# cw312_sam4s.net
KiCad netlist of a schematic drawn in Altium Designer
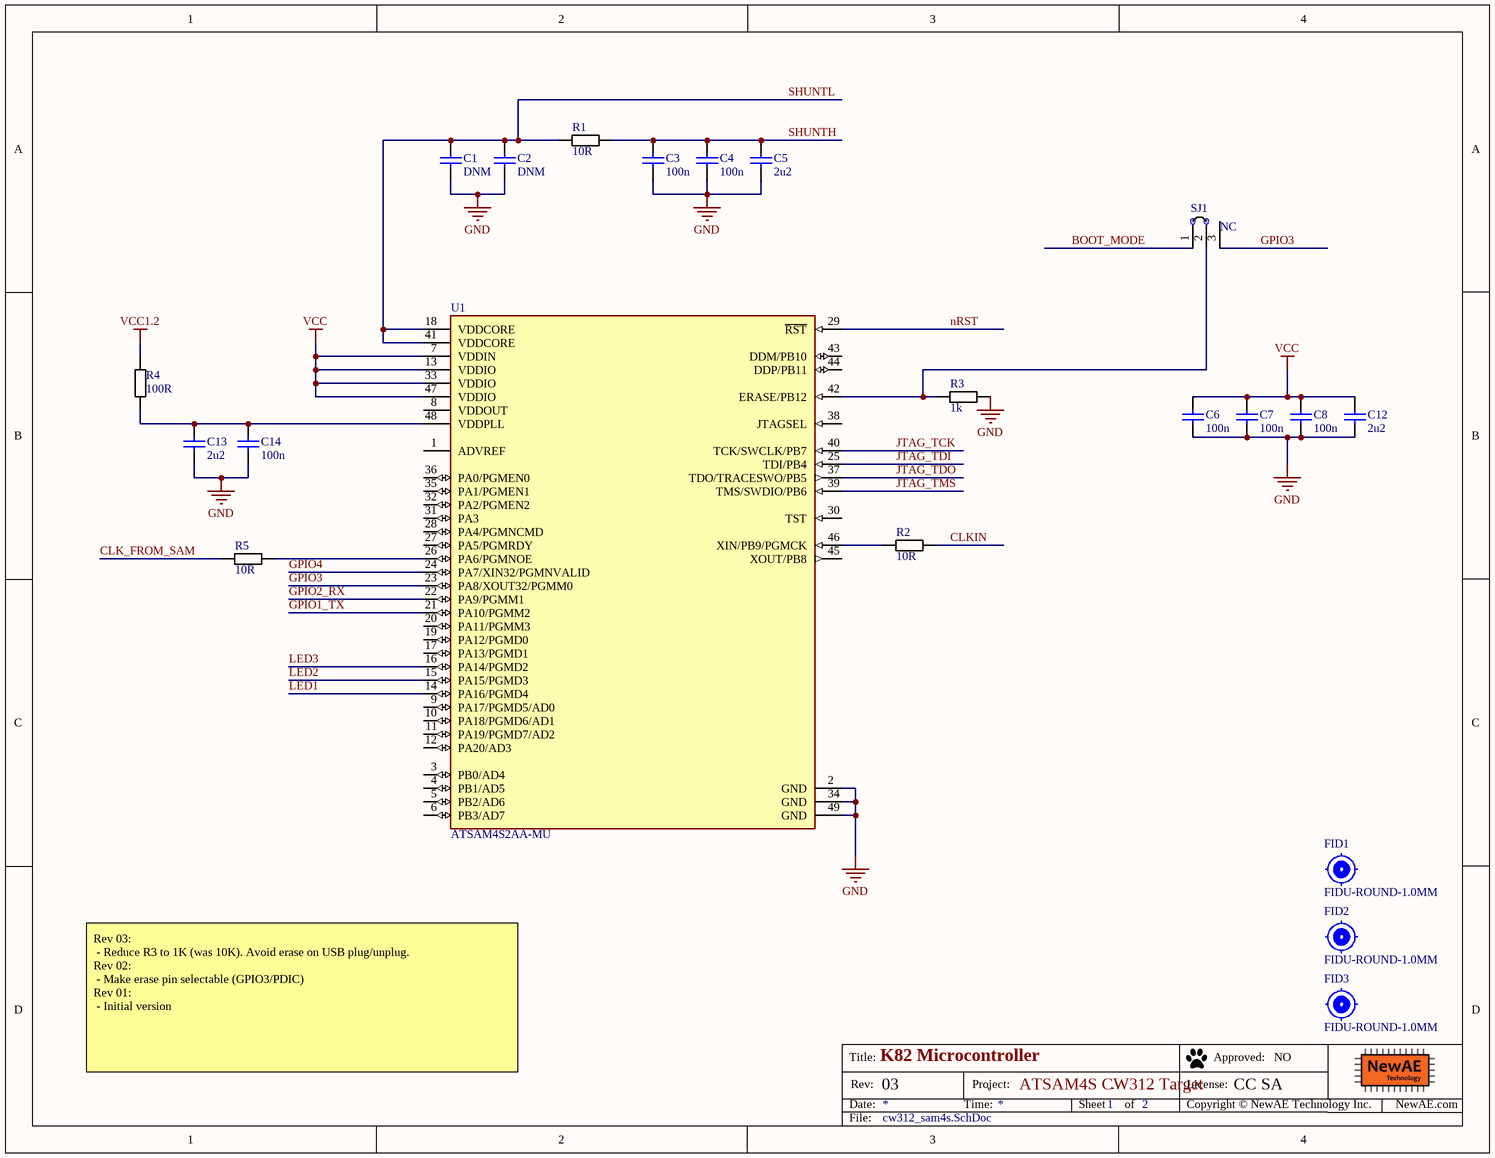
[diagram p0: cw312_sam4s.SchDoc]

(export (version "E")
  (design (tool "Eeschema 10.0.6"))
  (components
    (comp (ref "C1")
      (value "DNM")
      (footprint "CAPC0603_M")
      (fields (field (name "PART NUMBER") "CCHIP-100n-0603"))
      (libsource (lib "NewAE_AltiumLib") (part "CAP"))
    )
    (comp (ref "C2")
      (value "DNM")
      (footprint "CAPC0603_M")
      (fields (field (name "PART NUMBER") "CCHIP-100n-0603"))
      (libsource (lib "NewAE_AltiumLib") (part "CAP"))
    )
    (comp (ref "C3")
      (value "100n")
      (footprint "CAPC0603_M")
      (description "100n, 0603")
      (fields (field (name "PART NUMBER") "CCHIP-100n-0603"))
      (libsource (lib "NewAE_AltiumLib") (part "CAP"))
    )
    (comp (ref "C4")
      (value "100n")
      (footprint "CAPC0603_M")
      (description "100n, 0603")
      (fields (field (name "PART NUMBER") "CCHIP-100n-0603"))
      (libsource (lib "NewAE_AltiumLib") (part "CAP"))
    )
    (comp (ref "C5")
      (value "2u2")
      (footprint "CAPC0603_M")
      (description "2u2, 0603")
      (fields (field (name "PART NUMBER") "CCHIP-2u2-0603"))
      (libsource (lib "NewAE_AltiumLib") (part "CAP"))
    )
    (comp (ref "C6")
      (value "100n")
      (footprint "CAPC0603_M")
      (description "100n, 0603")
      (fields (field (name "PART NUMBER") "CCHIP-100n-0603"))
      (libsource (lib "NewAE_AltiumLib") (part "CAP"))
    )
    (comp (ref "C7")
      (value "100n")
      (footprint "CAPC0603_M")
      (description "100n, 0603")
      (fields (field (name "PART NUMBER") "CCHIP-100n-0603"))
      (libsource (lib "NewAE_AltiumLib") (part "CAP"))
    )
    (comp (ref "C8")
      (value "100n")
      (footprint "CAPC0603_M")
      (description "100n, 0603")
      (fields (field (name "PART NUMBER") "CCHIP-100n-0603"))
      (libsource (lib "NewAE_AltiumLib") (part "CAP"))
    )
    (comp (ref "C12")
      (value "2u2")
      (footprint "CAPC0603_M")
      (description "2u2, 0603")
      (fields (field (name "PART NUMBER") "CCHIP-2u2-0603"))
      (libsource (lib "NewAE_AltiumLib") (part "CAP"))
    )
    (comp (ref "C13")
      (value "2u2")
      (footprint "CAPC0603_M")
      (description "2u2, 0603")
      (fields (field (name "PART NUMBER") "CCHIP-2u2-0603"))
      (libsource (lib "NewAE_AltiumLib") (part "CAP"))
    )
    (comp (ref "C14")
      (value "100n")
      (footprint "CAPC0603_M")
      (description "100n, 0603")
      (fields (field (name "PART NUMBER") "CCHIP-100n-0603"))
      (libsource (lib "NewAE_AltiumLib") (part "CAP"))
    )
    (comp (ref "FID1")
      (value "FIDU-ROUND-1.0MM")
      (footprint "FIDU-ROUND-1.0mm")
      (description "ROUND FIDUCIAL")
      (libsource (lib "NewAE_AltiumLib") (part "FIDU-ROUND-1.0MM"))
    )
    (comp (ref "FID2")
      (value "FIDU-ROUND-1.0MM")
      (footprint "FIDU-ROUND-1.0mm")
      (description "ROUND FIDUCIAL")
      (libsource (lib "NewAE_AltiumLib") (part "FIDU-ROUND-1.0MM"))
    )
    (comp (ref "FID3")
      (value "FIDU-ROUND-1.0MM")
      (footprint "FIDU-ROUND-1.0mm")
      (description "ROUND FIDUCIAL")
      (libsource (lib "NewAE_AltiumLib") (part "FIDU-ROUND-1.0MM"))
    )
    (comp (ref "R1")
      (value "10R")
      (footprint "RESC1608X55N")
      (description "10R res, 0603, 1%, 1/10W")
      (fields (field (name "PART NUMBER") "RCHIP-10R-0603") (field (name "TOLERANCE") "1%"))
      (libsource (lib "") (part "RES-EU_1"))
    )
    (comp (ref "R2")
      (value "10R")
      (footprint "RESC1608X55N")
      (description "10R res, 0603, 1%, 1/10W")
      (fields (field (name "PART NUMBER") "RCHIP-10R-0603") (field (name "TOLERANCE") "1%"))
      (libsource (lib "NewAE_AltiumLib") (part "RES-EU"))
    )
    (comp (ref "R3")
      (value "1k")
      (footprint "RESC1608X55N")
      (description "1k res, 0603, 1%, 1/10W")
      (fields (field (name "PART NUMBER") "RCHIP-1K-0603") (field (name "TOLERANCE") "1%"))
      (libsource (lib "") (part "RES-EU_1"))
    )
    (comp (ref "R4")
      (value "100R")
      (footprint "RESC1608X55N")
      (description "100R res, 0603, 1%, 1/10W")
      (fields (field (name "PART NUMBER") "RCHIP-100R-0603") (field (name "TOLERANCE") "1%"))
      (libsource (lib "") (part "RES-EU_2"))
    )
    (comp (ref "R5")
      (value "10R")
      (footprint "RESC1608X55N")
      (description "10R res, 0603, 1%, 1/10W")
      (fields (field (name "PART NUMBER") "RCHIP-10R-0603") (field (name "TOLERANCE") "1%"))
      (libsource (lib "NewAE_AltiumLib") (part "RES-EU"))
    )
    (comp (ref "SJ1")
      (value "NC")
      (footprint "SJ_3S_NC12")
      (description "Solder Jumper, NC")
      (fields (field (name "PART NUMBER") "SJ_3S_12JMP"))
      (libsource (lib "NewAE_AltiumLib") (part "SJ_3S_12JMP"))
    )
    (comp (ref "U1")
      (value "ATSAM4S2AA-MU")
      (footprint "QFN50P700X700X100_HS-49M")
      (description "ATSAM4S, 128KB FLASH, 48QFN")
      (libsource (lib "NewAE_AltiumLib") (part "ATSAM4S2AA"))
    )
  )
  (nets
    (net (code "1") (name "/BOOT_MODE") (class "Default")
      (node (ref "SJ1") (pin "1") (pinfunction "1_1") (pintype "passive"))
    )
    (net (code "2") (name "/CLKIN") (class "Default")
      (node (ref "R2") (pin "1") (pinfunction "1_1") (pintype "passive"))
    )
    (net (code "3") (name "/CLK_FROM_SAM") (class "Default")
      (node (ref "R5") (pin "2") (pinfunction "2_2") (pintype "passive"))
    )
    (net (code "4") (name "/GPIO1_TX") (class "Default")
      (node (ref "U1") (pin "21") (pinfunction "PA10/PGMM2_21") (pintype "bidirectional"))
    )
    (net (code "5") (name "/GPIO2_RX") (class "Default")
      (node (ref "U1") (pin "22") (pinfunction "PA9/PGMM1_22") (pintype "bidirectional"))
    )
    (net (code "6") (name "/GPIO3") (class "Default")
      (node (ref "SJ1") (pin "3") (pinfunction "3_3") (pintype "passive"))
      (node (ref "U1") (pin "23") (pinfunction "PA8/XOUT32/PGMM0_23") (pintype "bidirectional"))
    )
    (net (code "7") (name "/GPIO4") (class "Default")
      (node (ref "U1") (pin "24") (pinfunction "PA7/XIN32/PGMNVALID_24") (pintype "bidirectional"))
    )
    (net (code "8") (name "/JTAG_TCK") (class "Default")
      (node (ref "U1") (pin "40") (pinfunction "TCK/SWCLK/PB7_40") (pintype "input"))
    )
    (net (code "9") (name "/JTAG_TDI") (class "Default")
      (node (ref "U1") (pin "25") (pinfunction "TDI/PB4_25") (pintype "input"))
    )
    (net (code "10") (name "/JTAG_TDO") (class "Default")
      (node (ref "U1") (pin "37") (pinfunction "TDO/TRACESWO/PB5_37") (pintype "output"))
    )
    (net (code "11") (name "/JTAG_TMS") (class "Default")
      (node (ref "U1") (pin "39") (pinfunction "TMS/SWDIO/PB6_39") (pintype "input"))
    )
    (net (code "12") (name "/LED1") (class "Default")
      (node (ref "U1") (pin "14") (pinfunction "PA16/PGMD4_14") (pintype "bidirectional"))
    )
    (net (code "13") (name "/LED2") (class "Default")
      (node (ref "U1") (pin "15") (pinfunction "PA15/PGMD3_15") (pintype "bidirectional"))
    )
    (net (code "14") (name "/LED3") (class "Default")
      (node (ref "U1") (pin "16") (pinfunction "PA14/PGMD2_16") (pintype "bidirectional"))
    )
    (net (code "15") (name "/SHUNTH") (class "Default")
      (node (ref "C3") (pin "1") (pinfunction "1_1") (pintype "passive"))
      (node (ref "C4") (pin "1") (pinfunction "1_1") (pintype "passive"))
      (node (ref "C5") (pin "1") (pinfunction "1_1") (pintype "passive"))
      (node (ref "R1") (pin "2") (pinfunction "2_2") (pintype "passive"))
    )
    (net (code "16") (name "/SHUNTL") (class "Default")
      (node (ref "C1") (pin "1") (pinfunction "1_1") (pintype "passive"))
      (node (ref "C2") (pin "1") (pinfunction "1_1") (pintype "passive"))
      (node (ref "R1") (pin "1") (pinfunction "1_1") (pintype "passive"))
      (node (ref "U1") (pin "18") (pinfunction "VDDCORE_18") (pintype "power_in"))
      (node (ref "U1") (pin "41") (pinfunction "VDDCORE_41") (pintype "power_in"))
    )
    (net (code "17") (name "/nRST") (class "Default")
      (node (ref "U1") (pin "29") (pinfunction "~{RST}_29") (pintype "input"))
    )
    (net (code "18") (name "GND") (class "Default")
      (node (ref "C1") (pin "2") (pinfunction "2_2") (pintype "passive"))
      (node (ref "C12") (pin "2") (pinfunction "2_2") (pintype "passive"))
      (node (ref "C13") (pin "2") (pinfunction "2_2") (pintype "passive"))
      (node (ref "C14") (pin "2") (pinfunction "2_2") (pintype "passive"))
      (node (ref "C2") (pin "2") (pinfunction "2_2") (pintype "passive"))
      (node (ref "C3") (pin "2") (pinfunction "2_2") (pintype "passive"))
      (node (ref "C4") (pin "2") (pinfunction "2_2") (pintype "passive"))
      (node (ref "C5") (pin "2") (pinfunction "2_2") (pintype "passive"))
      (node (ref "C6") (pin "2") (pinfunction "2_2") (pintype "passive"))
      (node (ref "C7") (pin "2") (pinfunction "2_2") (pintype "passive"))
      (node (ref "C8") (pin "2") (pinfunction "2_2") (pintype "passive"))
      (node (ref "R3") (pin "2") (pinfunction "2_2") (pintype "passive"))
      (node (ref "U1") (pin "2") (pinfunction "GND_2") (pintype "power_in"))
      (node (ref "U1") (pin "34") (pinfunction "GND_34") (pintype "power_in"))
      (node (ref "U1") (pin "49") (pinfunction "GND_49") (pintype "power_in"))
    )
    (net (code "19") (name "Net-(U1-ERASE{slash}PB12)") (class "Default")
      (node (ref "R3") (pin "1") (pinfunction "1_1") (pintype "passive"))
      (node (ref "SJ1") (pin "2") (pinfunction "2_2") (pintype "passive"))
      (node (ref "U1") (pin "42") (pinfunction "ERASE/PB12_42") (pintype "input"))
    )
    (net (code "20") (name "Net-(U1-PA6{slash}PGMNOE)") (class "Default")
      (node (ref "R5") (pin "1") (pinfunction "1_1") (pintype "passive"))
      (node (ref "U1") (pin "26") (pinfunction "PA6/PGMNOE_26") (pintype "bidirectional"))
    )
    (net (code "21") (name "Net-(U1-VDDPLL)") (class "Default")
      (node (ref "C13") (pin "1") (pinfunction "1_1") (pintype "passive"))
      (node (ref "C14") (pin "1") (pinfunction "1_1") (pintype "passive"))
      (node (ref "R4") (pin "2") (pinfunction "2_2") (pintype "passive"))
      (node (ref "U1") (pin "48") (pinfunction "VDDPLL_48") (pintype "power_in"))
    )
    (net (code "22") (name "Net-(U1-XIN{slash}PB9{slash}PGMCK)") (class "Default")
      (node (ref "R2") (pin "2") (pinfunction "2_2") (pintype "passive"))
      (node (ref "U1") (pin "46") (pinfunction "XIN/PB9/PGMCK_46") (pintype "input"))
    )
    (net (code "23") (name "VCC") (class "Default")
      (node (ref "C12") (pin "1") (pinfunction "1_1") (pintype "passive"))
      (node (ref "C6") (pin "1") (pinfunction "1_1") (pintype "passive"))
      (node (ref "C7") (pin "1") (pinfunction "1_1") (pintype "passive"))
      (node (ref "C8") (pin "1") (pinfunction "1_1") (pintype "passive"))
      (node (ref "U1") (pin "13") (pinfunction "VDDIO_13") (pintype "power_in"))
      (node (ref "U1") (pin "33") (pinfunction "VDDIO_33") (pintype "power_in"))
      (node (ref "U1") (pin "47") (pinfunction "VDDIO_47") (pintype "power_in"))
      (node (ref "U1") (pin "7") (pinfunction "VDDIN_7") (pintype "power_in"))
    )
    (net (code "24") (name "VCC1.2") (class "Default")
      (node (ref "R4") (pin "1") (pinfunction "1_1") (pintype "passive"))
    )
    (net (code "25") (name "unconnected-(U1-ADVREF-Pad1)") (class "Default")
      (node (ref "U1") (pin "1") (pinfunction "ADVREF_1") (pintype "power_in"))
    )
    (net (code "26") (name "unconnected-(U1-DDM{slash}PB10-Pad43)") (class "Default")
      (node (ref "U1") (pin "43") (pinfunction "DDM/PB10_43") (pintype "bidirectional"))
    )
    (net (code "27") (name "unconnected-(U1-DDP{slash}PB11-Pad44)") (class "Default")
      (node (ref "U1") (pin "44") (pinfunction "DDP/PB11_44") (pintype "bidirectional"))
    )
    (net (code "28") (name "unconnected-(U1-JTAGSEL-Pad38)") (class "Default")
      (node (ref "U1") (pin "38") (pinfunction "JTAGSEL_38") (pintype "input"))
    )
    (net (code "29") (name "unconnected-(U1-PA0{slash}PGMEN0-Pad36)") (class "Default")
      (node (ref "U1") (pin "36") (pinfunction "PA0/PGMEN0_36") (pintype "bidirectional"))
    )
    (net (code "30") (name "unconnected-(U1-PA1{slash}PGMEN1-Pad35)") (class "Default")
      (node (ref "U1") (pin "35") (pinfunction "PA1/PGMEN1_35") (pintype "bidirectional"))
    )
    (net (code "31") (name "unconnected-(U1-PA2{slash}PGMEN2-Pad32)") (class "Default")
      (node (ref "U1") (pin "32") (pinfunction "PA2/PGMEN2_32") (pintype "bidirectional"))
    )
    (net (code "32") (name "unconnected-(U1-PA3-Pad31)") (class "Default")
      (node (ref "U1") (pin "31") (pinfunction "PA3_31") (pintype "bidirectional"))
    )
    (net (code "33") (name "unconnected-(U1-PA4{slash}PGMNCMD-Pad28)") (class "Default")
      (node (ref "U1") (pin "28") (pinfunction "PA4/PGMNCMD_28") (pintype "bidirectional"))
    )
    (net (code "34") (name "unconnected-(U1-PA5{slash}PGMRDY-Pad27)") (class "Default")
      (node (ref "U1") (pin "27") (pinfunction "PA5/PGMRDY_27") (pintype "bidirectional"))
    )
    (net (code "35") (name "unconnected-(U1-PA11{slash}PGMM3-Pad20)") (class "Default")
      (node (ref "U1") (pin "20") (pinfunction "PA11/PGMM3_20") (pintype "bidirectional"))
    )
    (net (code "36") (name "unconnected-(U1-PA12{slash}PGMD0-Pad19)") (class "Default")
      (node (ref "U1") (pin "19") (pinfunction "PA12/PGMD0_19") (pintype "bidirectional"))
    )
    (net (code "37") (name "unconnected-(U1-PA13{slash}PGMD1-Pad17)") (class "Default")
      (node (ref "U1") (pin "17") (pinfunction "PA13/PGMD1_17") (pintype "bidirectional"))
    )
    (net (code "38") (name "unconnected-(U1-PA17{slash}PGMD5{slash}AD0-Pad9)") (class "Default")
      (node (ref "U1") (pin "9") (pinfunction "PA17/PGMD5/AD0_9") (pintype "bidirectional"))
    )
    (net (code "39") (name "unconnected-(U1-PA18{slash}PGMD6{slash}AD1-Pad10)") (class "Default")
      (node (ref "U1") (pin "10") (pinfunction "PA18/PGMD6/AD1_10") (pintype "bidirectional"))
    )
    (net (code "40") (name "unconnected-(U1-PA19{slash}PGMD7{slash}AD2-Pad11)") (class "Default")
      (node (ref "U1") (pin "11") (pinfunction "PA19/PGMD7/AD2_11") (pintype "bidirectional"))
    )
    (net (code "41") (name "unconnected-(U1-PA20{slash}AD3-Pad12)") (class "Default")
      (node (ref "U1") (pin "12") (pinfunction "PA20/AD3_12") (pintype "bidirectional"))
    )
    (net (code "42") (name "unconnected-(U1-PB0{slash}AD4-Pad3)") (class "Default")
      (node (ref "U1") (pin "3") (pinfunction "PB0/AD4_3") (pintype "bidirectional"))
    )
    (net (code "43") (name "unconnected-(U1-PB1{slash}AD5-Pad4)") (class "Default")
      (node (ref "U1") (pin "4") (pinfunction "PB1/AD5_4") (pintype "bidirectional"))
    )
    (net (code "44") (name "unconnected-(U1-PB2{slash}AD6-Pad5)") (class "Default")
      (node (ref "U1") (pin "5") (pinfunction "PB2/AD6_5") (pintype "bidirectional"))
    )
    (net (code "45") (name "unconnected-(U1-PB3{slash}AD7-Pad6)") (class "Default")
      (node (ref "U1") (pin "6") (pinfunction "PB3/AD7_6") (pintype "bidirectional"))
    )
    (net (code "46") (name "unconnected-(U1-TST-Pad30)") (class "Default")
      (node (ref "U1") (pin "30") (pinfunction "TST_30") (pintype "input"))
    )
    (net (code "47") (name "unconnected-(U1-VDDOUT-Pad8)") (class "Default")
      (node (ref "U1") (pin "8") (pinfunction "VDDOUT_8") (pintype "power_in"))
    )
    (net (code "48") (name "unconnected-(U1-XOUT{slash}PB8-Pad45)") (class "Default")
      (node (ref "U1") (pin "45") (pinfunction "XOUT/PB8_45") (pintype "output"))
    )
  )
)
